# CAN.net
KiCad netlist of a schematic drawn in Altium Designer
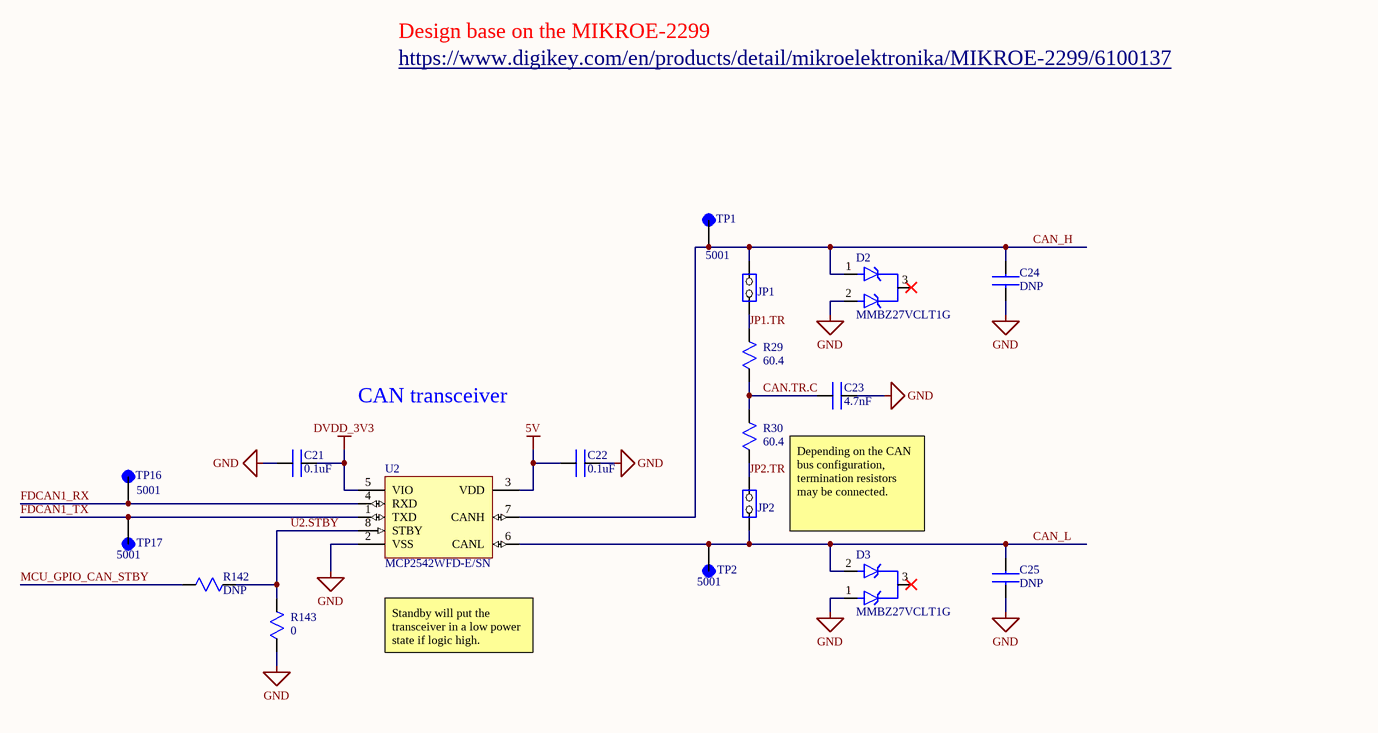
[diagram p0: CAN.SchDoc]

(export (version "E")
  (design (tool "Eeschema 10.0.6"))
  (components
    (comp (ref "C21")
      (value "0.1uF")
      (footprint "0603")
      (description "CAP CER 0.1UF 100V X7R 0603")
      (fields (field (name "MFG") "SAMSUNG"))
      (libsource (lib "Myomo_SCH_Library") (part "C_0603_CER_0.1uF_100V_X7R"))
    )
    (comp (ref "C22")
      (value "0.1uF")
      (footprint "0603")
      (description "CAP CER 0.1UF 100V X7R 0603")
      (fields (field (name "MFG") "SAMSUNG"))
      (libsource (lib "Myomo_SCH_Library") (part "C_0603_CER_0.1uF_100V_X7R"))
    )
    (comp (ref "C23")
      (value "4.7nF")
      (footprint "0603")
      (description "CAP CER 4700PF 100V X7R 0603")
      (fields (field (name "MFG") "SAMSUNG"))
      (libsource (lib "Myomo_SCH_Library") (part "C_0603_CER_4.7nF_100V_X7R"))
    )
    (comp (ref "C24")
      (value "DNP")
      (footprint "0603")
      (description "CAP CER 0603 DNP")
      (libsource (lib "Myomo_SCH_Library") (part "C_0603_DNP"))
    )
    (comp (ref "C25")
      (value "DNP")
      (footprint "0603")
      (description "CAP CER 0603 DNP")
      (libsource (lib "Myomo_SCH_Library") (part "C_0603_DNP"))
    )
    (comp (ref "D2")
      (value "MMBZ27VCLT1G")
      (footprint "D_TVS_38V_40W")
      (description "TVS DIODE 22VWM 38VC SOT23-3")
      (fields (field (name "MFG") "Onsemi"))
      (libsource (lib "Myomo_SCH_Library") (part "D_TVS_38V_40W"))
    )
    (comp (ref "D3")
      (value "MMBZ27VCLT1G")
      (footprint "D_TVS_38V_40W")
      (description "TVS DIODE 22VWM 38VC SOT23-3")
      (fields (field (name "MFG") "Onsemi"))
      (libsource (lib "Myomo_SCH_Library") (part "D_TVS_38V_40W"))
    )
    (comp (ref "JP1")
      (value "JP_1x2_TSW-102-07-F-S")
      (footprint "JP_1x2_TSW-102-07-F-S")
      (description "CONN HEADER VERT 2POS 2.54MM")
      (fields (field (name "MFG") "SAMTEC"))
      (libsource (lib "Myomo_SCH_Library") (part "JP_1x2_TSW-102-07-F-S"))
    )
    (comp (ref "JP2")
      (value "JP_1x2_TSW-102-07-F-S")
      (footprint "JP_1x2_TSW-102-07-F-S")
      (description "CONN HEADER VERT 2POS 2.54MM")
      (fields (field (name "MFG") "SAMTEC"))
      (libsource (lib "Myomo_SCH_Library") (part "JP_1x2_TSW-102-07-F-S"))
    )
    (comp (ref "R29")
      (value "60.4")
      (footprint "0603")
      (description "RES 60.4 OHM 1% 1/10W 0603")
      (fields (field (name "MFG") "YAGEO"))
      (libsource (lib "Myomo_SCH_Library") (part "R_0603_60.4_1%_1/10W"))
    )
    (comp (ref "R30")
      (value "60.4")
      (footprint "0603")
      (description "RES 60.4 OHM 1% 1/10W 0603")
      (fields (field (name "MFG") "YAGEO"))
      (libsource (lib "Myomo_SCH_Library") (part "R_0603_60.4_1%_1/10W"))
    )
    (comp (ref "R142")
      (value "DNP")
      (footprint "0402")
      (description "RES 0402 DNP")
      (libsource (lib "Myomo_SCH_Library") (part "R_0402_DNP"))
    )
    (comp (ref "R143")
      (value "0")
      (footprint "0402")
      (description "RES 0 OHM JUMPER 1/10W 0402")
      (fields (field (name "MFG") "YAGEO"))
      (libsource (lib "Myomo_SCH_Library") (part "R_0402_0"))
    )
    (comp (ref "TP1")
      (value "5001")
      (footprint "TP_CLIP_BLK_5001")
      (description "PC TEST POINT MINIATURE BLACK")
      (fields (field (name "MFG") "Keystone Electronics"))
      (libsource (lib "Myomo_SCH_Library") (part "TP_CLIP_BLK_5001"))
    )
    (comp (ref "TP2")
      (value "5001")
      (footprint "TP_CLIP_BLK_5001")
      (description "PC TEST POINT MINIATURE BLACK")
      (fields (field (name "MFG") "Keystone Electronics"))
      (libsource (lib "Myomo_SCH_Library") (part "TP_CLIP_BLK_5001"))
    )
    (comp (ref "TP16")
      (value "5001")
      (footprint "TP_CLIP_BLK_5001")
      (description "PC TEST POINT MINIATURE BLACK")
      (fields (field (name "MFG") "Keystone Electronics"))
      (libsource (lib "Myomo_SCH_Library") (part "TP_CLIP_BLK_5001"))
    )
    (comp (ref "TP17")
      (value "5001")
      (footprint "TP_CLIP_BLK_5001")
      (description "PC TEST POINT MINIATURE BLACK")
      (fields (field (name "MFG") "Keystone Electronics"))
      (libsource (lib "Myomo_SCH_Library") (part "TP_CLIP_BLK_5001"))
    )
    (comp (ref "U2")
      (value "MCP2542WFD-E/SN")
      (footprint "U_MCP2542WFD-E/SN")
      (description "IC CAN TRANSCEIVER 1/1 8SOIC")
      (fields (field (name "MFG") "Microchip"))
      (libsource (lib "Myomo_SCH_Library") (part "U_MCP2542WFD-E/SN"))
    )
  )
  (nets
    (net (code "1") (name "/CAN.TR.C") (class "Default")
      (node (ref "C23") (pin "1") (pinfunction "1_1") (pintype "passive"))
      (node (ref "R29") (pin "2") (pinfunction "2_2") (pintype "passive"))
      (node (ref "R30") (pin "1") (pinfunction "1_1") (pintype "passive"))
    )
    (net (code "2") (name "/CAN_H") (class "Default")
      (node (ref "C24") (pin "1") (pinfunction "1_1") (pintype "passive"))
      (node (ref "D2") (pin "1") (pinfunction "A1_1") (pintype "passive"))
      (node (ref "JP1") (pin "1") (pinfunction "1_1") (pintype "passive"))
      (node (ref "TP1") (pin "TP") (pinfunction "TP_TP") (pintype "passive"))
      (node (ref "U2") (pin "7") (pinfunction "CANH_7") (pintype "bidirectional"))
    )
    (net (code "3") (name "/CAN_L") (class "Default")
      (node (ref "C25") (pin "1") (pinfunction "1_1") (pintype "passive"))
      (node (ref "D3") (pin "2") (pinfunction "A2_2") (pintype "passive"))
      (node (ref "JP2") (pin "1") (pinfunction "1_1") (pintype "passive"))
      (node (ref "TP2") (pin "TP") (pinfunction "TP_TP") (pintype "passive"))
      (node (ref "U2") (pin "6") (pinfunction "CANL_6") (pintype "bidirectional"))
    )
    (net (code "4") (name "/FDCAN1_RX") (class "Default")
      (node (ref "TP16") (pin "TP") (pinfunction "TP_TP") (pintype "passive"))
      (node (ref "U2") (pin "4") (pinfunction "RXD_4") (pintype "bidirectional"))
    )
    (net (code "5") (name "/FDCAN1_TX") (class "Default")
      (node (ref "TP17") (pin "TP") (pinfunction "TP_TP") (pintype "passive"))
      (node (ref "U2") (pin "1") (pinfunction "TXD_1") (pintype "bidirectional"))
    )
    (net (code "6") (name "/JP1.TR") (class "Default")
      (node (ref "JP1") (pin "2") (pinfunction "2_2") (pintype "passive"))
      (node (ref "R29") (pin "1") (pinfunction "1_1") (pintype "passive"))
    )
    (net (code "7") (name "/JP2.TR") (class "Default")
      (node (ref "JP2") (pin "2") (pinfunction "2_2") (pintype "passive"))
      (node (ref "R30") (pin "2") (pinfunction "2_2") (pintype "passive"))
    )
    (net (code "8") (name "/MCU_GPIO_CAN_STBY") (class "Default")
      (node (ref "R142") (pin "1") (pinfunction "1_1") (pintype "passive"))
    )
    (net (code "9") (name "/U2.STBY") (class "Default")
      (node (ref "R142") (pin "2") (pinfunction "2_2") (pintype "passive"))
      (node (ref "R143") (pin "1") (pinfunction "1_1") (pintype "passive"))
      (node (ref "U2") (pin "8") (pinfunction "STBY_8") (pintype "input"))
    )
    (net (code "10") (name "5V") (class "Default")
      (node (ref "C22") (pin "1") (pinfunction "1_1") (pintype "passive"))
      (node (ref "U2") (pin "3") (pinfunction "VDD_3") (pintype "power_in"))
    )
    (net (code "11") (name "DVDD_3V3") (class "Default")
      (node (ref "C21") (pin "2") (pinfunction "2_2") (pintype "passive"))
      (node (ref "U2") (pin "5") (pinfunction "VIO_5") (pintype "power_in"))
    )
    (net (code "12") (name "GND") (class "Default")
      (node (ref "C21") (pin "1") (pinfunction "1_1") (pintype "passive"))
      (node (ref "C22") (pin "2") (pinfunction "2_2") (pintype "passive"))
      (node (ref "C23") (pin "2") (pinfunction "2_2") (pintype "passive"))
      (node (ref "C24") (pin "2") (pinfunction "2_2") (pintype "passive"))
      (node (ref "C25") (pin "2") (pinfunction "2_2") (pintype "passive"))
      (node (ref "D2") (pin "2") (pinfunction "A2_2") (pintype "passive"))
      (node (ref "D3") (pin "1") (pinfunction "A1_1") (pintype "passive"))
      (node (ref "R143") (pin "2") (pinfunction "2_2") (pintype "passive"))
      (node (ref "U2") (pin "2") (pinfunction "VSS_2") (pintype "power_in"))
    )
    (net (code "13") (name "unconnected-(D2-K-Pad3)") (class "Default")
      (node (ref "D2") (pin "3") (pinfunction "K_3") (pintype "passive+no_connect"))
    )
    (net (code "14") (name "unconnected-(D3-K-Pad3)") (class "Default")
      (node (ref "D3") (pin "3") (pinfunction "K_3") (pintype "passive+no_connect"))
    )
  )
)
